# HV_Sense.net
KiCad netlist of a schematic drawn in Altium Designer
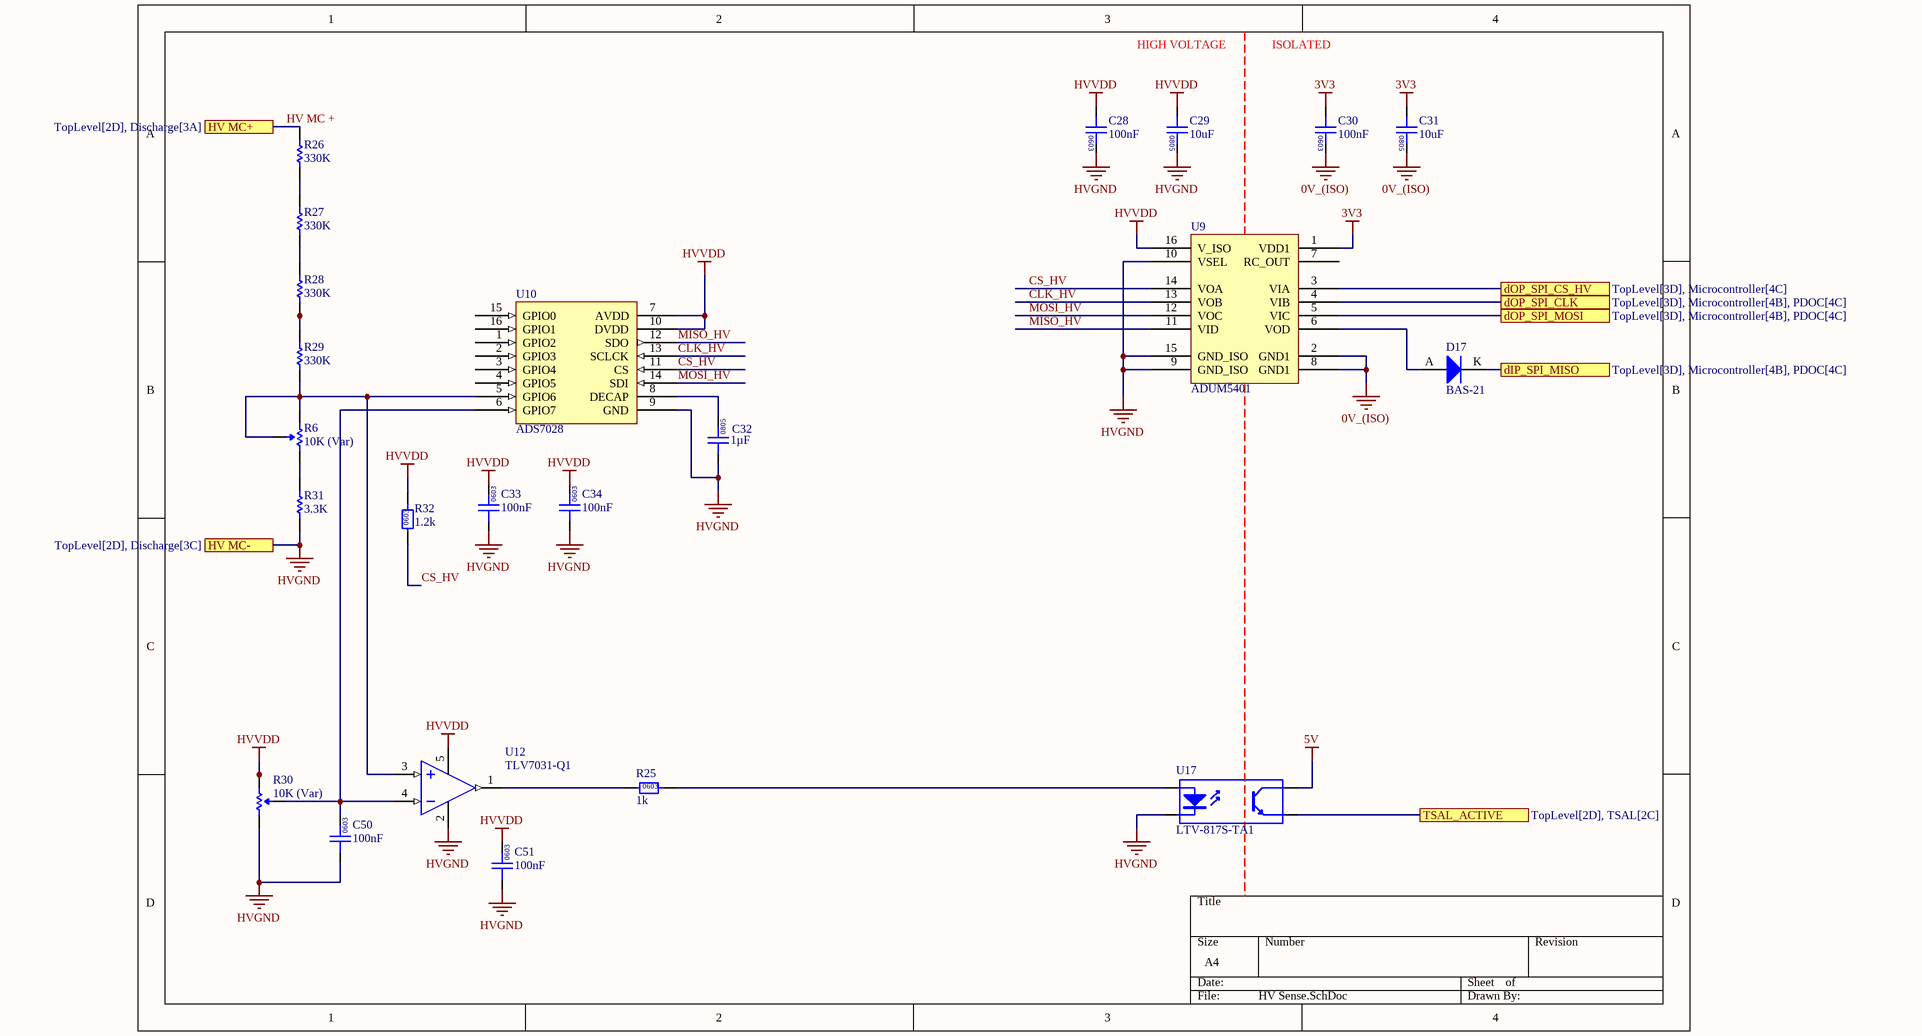
[diagram p0: HV Sense.SchDoc]

(export (version "E")
  (design (tool "Eeschema 10.0.6"))
  (components
    (comp (ref "C28")
      (value "100nF")
      (footprint "0603")
      (fields
        (field (name "PART NUMBER") "GCM188L81H104KA57D")
        (field (name "MANUFACTURER") "muRata")
        (field (name "TOLERANCE") "±10%")
      )
      (libsource (lib "ts_standard_library") (part "Capacitor 0603"))
    )
    (comp (ref "C29")
      (value "10uF")
      (footprint "0805")
      (fields
        (field (name "PART NUMBER") "GRM21BR6YA106KE43L")
        (field (name "MANUFACTURER") "muRata")
        (field (name "TOLERANCE") "10%")
      )
      (libsource (lib "ts_standard_library") (part "Capacitor 0805"))
    )
    (comp (ref "C30")
      (value "100nF")
      (footprint "0603")
      (fields
        (field (name "PART NUMBER") "GCM188L81H104KA57D")
        (field (name "MANUFACTURER") "muRata")
        (field (name "TOLERANCE") "±10%")
      )
      (libsource (lib "ts_standard_library") (part "Capacitor 0603"))
    )
    (comp (ref "C31")
      (value "10uF")
      (footprint "0805")
      (fields
        (field (name "PART NUMBER") "GRM21BR6YA106KE43L")
        (field (name "MANUFACTURER") "muRata")
        (field (name "TOLERANCE") "10%")
      )
      (libsource (lib "ts_standard_library") (part "Capacitor 0805"))
    )
    (comp (ref "C32")
      (value "1µF")
      (footprint "0805")
      (fields
        (field (name "PART NUMBER") "GCM21BR71H105KA03L")
        (field (name "MANUFACTURER") "muRata")
        (field (name "TOLERANCE") "±10%")
      )
      (libsource (lib "ts_standard_library") (part "Capacitor 0805"))
    )
    (comp (ref "C33")
      (value "100nF")
      (footprint "0603")
      (fields
        (field (name "PART NUMBER") "GCM188L81H104KA57D")
        (field (name "MANUFACTURER") "muRata")
        (field (name "TOLERANCE") "±10%")
      )
      (libsource (lib "ts_standard_library") (part "Capacitor 0603"))
    )
    (comp (ref "C34")
      (value "100nF")
      (footprint "0603")
      (fields
        (field (name "PART NUMBER") "GCM188L81H104KA57D")
        (field (name "MANUFACTURER") "muRata")
        (field (name "TOLERANCE") "±10%")
      )
      (libsource (lib "ts_standard_library") (part "Capacitor 0603"))
    )
    (comp (ref "C50")
      (value "100nF")
      (footprint "0603")
      (fields
        (field (name "PART NUMBER") "GCM188L81H104KA57D")
        (field (name "MANUFACTURER") "muRata")
        (field (name "TOLERANCE") "±10%")
      )
      (libsource (lib "ts_standard_library") (part "Capacitor 0603"))
    )
    (comp (ref "C51")
      (value "100nF")
      (footprint "0603")
      (fields
        (field (name "PART NUMBER") "GCM188L81H104KA57D")
        (field (name "MANUFACTURER") "muRata")
        (field (name "TOLERANCE") "±10%")
      )
      (libsource (lib "ts_standard_library") (part "Capacitor 0603"))
    )
    (comp (ref "D17")
      (value "BAS-21")
      (footprint "NEXPERIA_SOT23")
      (fields (field (name "MANUFACTURER") "Nexperia USA Inc."))
      (libsource (lib "ts_standard_library") (part "Diode"))
    )
    (comp (ref "R6")
      (value "10K (Var)")
      (footprint "B 3296")
      (fields
        (field (name "PART NUMBER") "3296W-1-103LF")
        (field (name "MANUFACTURER") "Bournes Inc")
        (field (name "TOLERANCE") "0.1")
      )
      (libsource (lib "ts_standard_library") (part "Resistor (Potentiometer)"))
    )
    (comp (ref "R25")
      (value "1k")
      (footprint "0603")
      (fields
        (field (name "PART NUMBER") "RC0603FR-071KL")
        (field (name "MANUFACTURER") "YAGEO")
        (field (name "TOLERANCE") "0.01")
      )
      (libsource (lib "ts_standard_library") (part "Resistor 0603"))
    )
    (comp (ref "R26")
      (value "330K")
      (footprint "VB 0207")
      (fields
        (field (name "PART NUMBER") "MMB02070C3303FB200")
        (field (name "MANUFACTURER") "Vishay Beyschlag")
        (field (name "TOLERANCE") "0.01")
      )
      (libsource (lib "ts_standard_library") (part "Resistor"))
    )
    (comp (ref "R27")
      (value "330K")
      (footprint "VB 0207")
      (fields
        (field (name "PART NUMBER") "MMB02070C3303FB200")
        (field (name "MANUFACTURER") "Vishay Beyschlag")
        (field (name "TOLERANCE") "0.01")
      )
      (libsource (lib "ts_standard_library") (part "Resistor"))
    )
    (comp (ref "R28")
      (value "330K")
      (footprint "VB 0207")
      (fields
        (field (name "PART NUMBER") "MMB02070C3303FB200")
        (field (name "MANUFACTURER") "Vishay Beyschlag")
        (field (name "TOLERANCE") "0.01")
      )
      (libsource (lib "ts_standard_library") (part "Resistor"))
    )
    (comp (ref "R29")
      (value "330K")
      (footprint "VB 0207")
      (fields
        (field (name "PART NUMBER") "MMB02070C3303FB200")
        (field (name "MANUFACTURER") "Vishay Beyschlag")
        (field (name "TOLERANCE") "0.01")
      )
      (libsource (lib "ts_standard_library") (part "Resistor"))
    )
    (comp (ref "R30")
      (value "10K (Var)")
      (footprint "B 3296")
      (fields
        (field (name "PART NUMBER") "3296W-1-103LF")
        (field (name "MANUFACTURER") "Bournes Inc")
        (field (name "TOLERANCE") "0.1")
      )
      (libsource (lib "ts_standard_library") (part "Resistor (Potentiometer)"))
    )
    (comp (ref "R31")
      (value "3.3K")
      (footprint "VB 0207")
      (fields
        (field (name "PART NUMBER") "MMB02070C3301FB200")
        (field (name "MANUFACTURER") "Vishay Beyschlag")
        (field (name "TOLERANCE") "0.01")
      )
      (libsource (lib "ts_20-standard-library") (part "Resistor"))
    )
    (comp (ref "R32")
      (value "1.2k")
      (footprint "0603")
      (fields
        (field (name "PART NUMBER") "RC0603JR-071K2L")
        (field (name "MANUFACTURER") "YAGEO")
        (field (name "TOLERANCE") "0.01")
      )
      (libsource (lib "ts_standard_library") (part "Resistor 0603"))
    )
    (comp (ref "U9")
      (value "ADUM5401")
      (footprint "AD 16-SOIC")
      (description "Quad Channel 2.5kV Digital Isolator with isoPower")
      (fields (field (name "MANUFACTURER") "Analogue Devices"))
      (libsource (lib "ts_standard_library") (part "ADUM5401"))
    )
    (comp (ref "U10")
      (value "ADS7028")
      (footprint "WFQN-16")
      (description "IC ADC 12BIT SAR 16WQFN")
      (fields (field (name "PART NUMBER") "ADS7028IRTER") (field (name "MANUFACTURER") "Texas Instruments"))
      (libsource (lib "ts_standard_library") (part "ADS7028IRTER"))
    )
    (comp (ref "U12")
      (value "TLV7031-Q1")
      (footprint "TI SOT-23-5")
      (fields
        (field (name "MANUFACTURER") "Texas Instruments")
        (field (name "DIGIKEY PART NUMBER") "296-TLV7031QDBVRQ1CT-ND")
      )
      (libsource (lib "ts_standard_library") (part "TLV7031-Q1"))
    )
    (comp (ref "U17")
      (value "LTV-817S-TA1")
      (footprint "ON 4-SMD")
      (description "35V 50ma Optocoupler (VF=1.2V)")
      (fields
        (field (name "MANUFACTURER") "Lite-On Inc")
        (field (name "DIGIKEY PART NUMBER") "160-1893-2-ND")
      )
      (libsource (lib "ts_20-standard-library") (part "LTV-817S-TA1"))
    )
  )
  (nets
    (net (code "1") (name "/CLK_HV") (class "Default")
      (node (ref "U10") (pin "13") (pinfunction "SCLCK_13") (pintype "input"))
      (node (ref "U9") (pin "13") (pinfunction "VOB_13") (pintype "passive"))
    )
    (net (code "2") (name "/CS_HV") (class "Default")
      (node (ref "R32") (pin "1") (pinfunction "1_1") (pintype "passive"))
      (node (ref "U10") (pin "11") (pinfunction "CS_11") (pintype "input"))
      (node (ref "U9") (pin "14") (pinfunction "VOA_14") (pintype "passive"))
    )
    (net (code "3") (name "/HV MC +") (class "Default")
      (node (ref "R26") (pin "2") (pinfunction "2_2") (pintype "passive"))
    )
    (net (code "4") (name "/MISO_HV") (class "Default")
      (node (ref "U10") (pin "12") (pinfunction "SDO_12") (pintype "output"))
      (node (ref "U9") (pin "11") (pinfunction "VID_11") (pintype "passive"))
    )
    (net (code "5") (name "/MOSI_HV") (class "Default")
      (node (ref "U10") (pin "14") (pinfunction "SDI_14") (pintype "input"))
      (node (ref "U9") (pin "12") (pinfunction "VOC_12") (pintype "passive"))
    )
    (net (code "6") (name "/TSAL_ACTIVE") (class "Default")
      (node (ref "U17") (pin "3") (pinfunction "E_3") (pintype "passive"))
    )
    (net (code "7") (name "/dIP_SPI_MISO") (class "Default")
      (node (ref "D17") (pin "K") (pinfunction "K_K") (pintype "passive"))
    )
    (net (code "8") (name "/dOP_SPI_CLK") (class "Default")
      (node (ref "U9") (pin "4") (pinfunction "VIB_4") (pintype "passive"))
    )
    (net (code "9") (name "/dOP_SPI_CS_HV") (class "Default")
      (node (ref "U9") (pin "3") (pinfunction "VIA_3") (pintype "passive"))
    )
    (net (code "10") (name "/dOP_SPI_MOSI") (class "Default")
      (node (ref "U9") (pin "5") (pinfunction "VIC_5") (pintype "passive"))
    )
    (net (code "11") (name "0V_(ISO)") (class "Default")
      (node (ref "C30") (pin "2") (pinfunction "2_2") (pintype "passive"))
      (node (ref "C31") (pin "2") (pinfunction "2_2") (pintype "passive"))
      (node (ref "U9") (pin "2") (pinfunction "GND1_2") (pintype "passive"))
      (node (ref "U9") (pin "8") (pinfunction "GND1_8") (pintype "passive"))
    )
    (net (code "12") (name "3V3") (class "Default")
      (node (ref "C30") (pin "1") (pinfunction "1_1") (pintype "passive"))
      (node (ref "C31") (pin "1") (pinfunction "1_1") (pintype "passive"))
      (node (ref "U9") (pin "1") (pinfunction "VDD1_1") (pintype "passive"))
    )
    (net (code "13") (name "5V") (class "Default")
      (node (ref "U17") (pin "4") (pinfunction "C_4") (pintype "passive"))
    )
    (net (code "14") (name "HVGND") (class "Default")
      (node (ref "C28") (pin "2") (pinfunction "2_2") (pintype "passive"))
      (node (ref "C29") (pin "2") (pinfunction "2_2") (pintype "passive"))
      (node (ref "C32") (pin "1") (pinfunction "1_1") (pintype "passive"))
      (node (ref "C33") (pin "1") (pinfunction "1_1") (pintype "passive"))
      (node (ref "C34") (pin "1") (pinfunction "1_1") (pintype "passive"))
      (node (ref "C50") (pin "1") (pinfunction "1_1") (pintype "passive"))
      (node (ref "C51") (pin "1") (pinfunction "1_1") (pintype "passive"))
      (node (ref "R30") (pin "3") (pinfunction "CW_3") (pintype "passive"))
      (node (ref "R31") (pin "1") (pinfunction "1_1") (pintype "passive"))
      (node (ref "U10") (pin "9") (pinfunction "GND_9") (pintype "power_in"))
      (node (ref "U12") (pin "2") (pinfunction "V-_2") (pintype "power_in"))
      (node (ref "U17") (pin "2") (pinfunction "K_2") (pintype "passive"))
      (node (ref "U9") (pin "10") (pinfunction "VSEL_10") (pintype "passive"))
      (node (ref "U9") (pin "15") (pinfunction "GND_ISO_15") (pintype "passive"))
      (node (ref "U9") (pin "9") (pinfunction "GND_ISO_9") (pintype "passive"))
    )
    (net (code "15") (name "HVVDD") (class "Default")
      (node (ref "C28") (pin "1") (pinfunction "1_1") (pintype "passive"))
      (node (ref "C29") (pin "1") (pinfunction "1_1") (pintype "passive"))
      (node (ref "C33") (pin "2") (pinfunction "2_2") (pintype "passive"))
      (node (ref "C34") (pin "2") (pinfunction "2_2") (pintype "passive"))
      (node (ref "C51") (pin "2") (pinfunction "2_2") (pintype "passive"))
      (node (ref "R30") (pin "1") (pinfunction "CCW_1") (pintype "passive"))
      (node (ref "R32") (pin "2") (pinfunction "2_2") (pintype "passive"))
      (node (ref "U10") (pin "10") (pinfunction "DVDD_10") (pintype "power_in"))
      (node (ref "U10") (pin "7") (pinfunction "AVDD_7") (pintype "power_in"))
      (node (ref "U12") (pin "5") (pinfunction "Vcc_5") (pintype "power_in"))
      (node (ref "U9") (pin "16") (pinfunction "V_ISO_16") (pintype "passive"))
    )
    (net (code "16") (name "Net-(R6-CCW)") (class "Default")
      (node (ref "R31") (pin "2") (pinfunction "2_2") (pintype "passive"))
      (node (ref "R6") (pin "1") (pinfunction "CCW_1") (pintype "passive"))
    )
    (net (code "17") (name "Net-(R6-CW)") (class "Default")
      (node (ref "R29") (pin "1") (pinfunction "1_1") (pintype "passive"))
      (node (ref "R6") (pin "2") (pinfunction "Wiper_2") (pintype "passive"))
      (node (ref "R6") (pin "3") (pinfunction "CW_3") (pintype "passive"))
      (node (ref "U10") (pin "5") (pinfunction "GPIO6_5") (pintype "input"))
      (node (ref "U12") (pin "3") (pinfunction "IN+_3") (pintype "input"))
    )
    (net (code "18") (name "Net-(R26-Pad1)") (class "Default")
      (node (ref "R26") (pin "1") (pinfunction "1_1") (pintype "passive"))
      (node (ref "R27") (pin "2") (pinfunction "2_2") (pintype "passive"))
    )
    (net (code "19") (name "Net-(R27-Pad1)") (class "Default")
      (node (ref "R27") (pin "1") (pinfunction "1_1") (pintype "passive"))
      (node (ref "R28") (pin "2") (pinfunction "2_2") (pintype "passive"))
    )
    (net (code "20") (name "Net-(R28-Pad1)") (class "Default")
      (node (ref "R28") (pin "1") (pinfunction "1_1") (pintype "passive"))
      (node (ref "R29") (pin "2") (pinfunction "2_2") (pintype "passive"))
    )
    (net (code "21") (name "Net-(R30-Wiper)") (class "Default")
      (node (ref "C50") (pin "2") (pinfunction "2_2") (pintype "passive"))
      (node (ref "R30") (pin "2") (pinfunction "Wiper_2") (pintype "passive"))
      (node (ref "U10") (pin "6") (pinfunction "GPIO7_6") (pintype "input"))
      (node (ref "U12") (pin "4") (pinfunction "IN-_4") (pintype "input"))
    )
    (net (code "22") (name "Net-(U9-VOD)") (class "Default")
      (node (ref "D17") (pin "A") (pinfunction "A_A") (pintype "passive"))
      (node (ref "U9") (pin "6") (pinfunction "VOD_6") (pintype "passive"))
    )
    (net (code "23") (name "Net-(U10-DECAP)") (class "Default")
      (node (ref "C32") (pin "2") (pinfunction "2_2") (pintype "passive"))
      (node (ref "U10") (pin "8") (pinfunction "DECAP_8") (pintype "power_in"))
    )
    (net (code "24") (name "Net-(U12-OUT)") (class "Default")
      (node (ref "R25") (pin "1") (pinfunction "1_1") (pintype "passive"))
      (node (ref "U12") (pin "1") (pinfunction "OUT_1") (pintype "output"))
    )
    (net (code "25") (name "Net-(U17-A)") (class "Default")
      (node (ref "R25") (pin "2") (pinfunction "2_2") (pintype "passive"))
      (node (ref "U17") (pin "1") (pinfunction "A_1") (pintype "passive"))
    )
    (net (code "26") (name "unconnected-(U9-RC_OUT-Pad7)") (class "Default")
      (node (ref "U9") (pin "7") (pinfunction "RC_OUT_7") (pintype "passive"))
    )
    (net (code "27") (name "unconnected-(U10-GPIO0-Pad15)") (class "Default")
      (node (ref "U10") (pin "15") (pinfunction "GPIO0_15") (pintype "input"))
    )
    (net (code "28") (name "unconnected-(U10-GPIO1-Pad16)") (class "Default")
      (node (ref "U10") (pin "16") (pinfunction "GPIO1_16") (pintype "input"))
    )
    (net (code "29") (name "unconnected-(U10-GPIO2-Pad1)") (class "Default")
      (node (ref "U10") (pin "1") (pinfunction "GPIO2_1") (pintype "input"))
    )
    (net (code "30") (name "unconnected-(U10-GPIO3-Pad2)") (class "Default")
      (node (ref "U10") (pin "2") (pinfunction "GPIO3_2") (pintype "input"))
    )
    (net (code "31") (name "unconnected-(U10-GPIO4-Pad3)") (class "Default")
      (node (ref "U10") (pin "3") (pinfunction "GPIO4_3") (pintype "input"))
    )
    (net (code "32") (name "unconnected-(U10-GPIO5-Pad4)") (class "Default")
      (node (ref "U10") (pin "4") (pinfunction "GPIO5_4") (pintype "input"))
    )
  )
)
